# ORD_FV1.net
KiCad netlist of a schematic drawn in Altium Designer
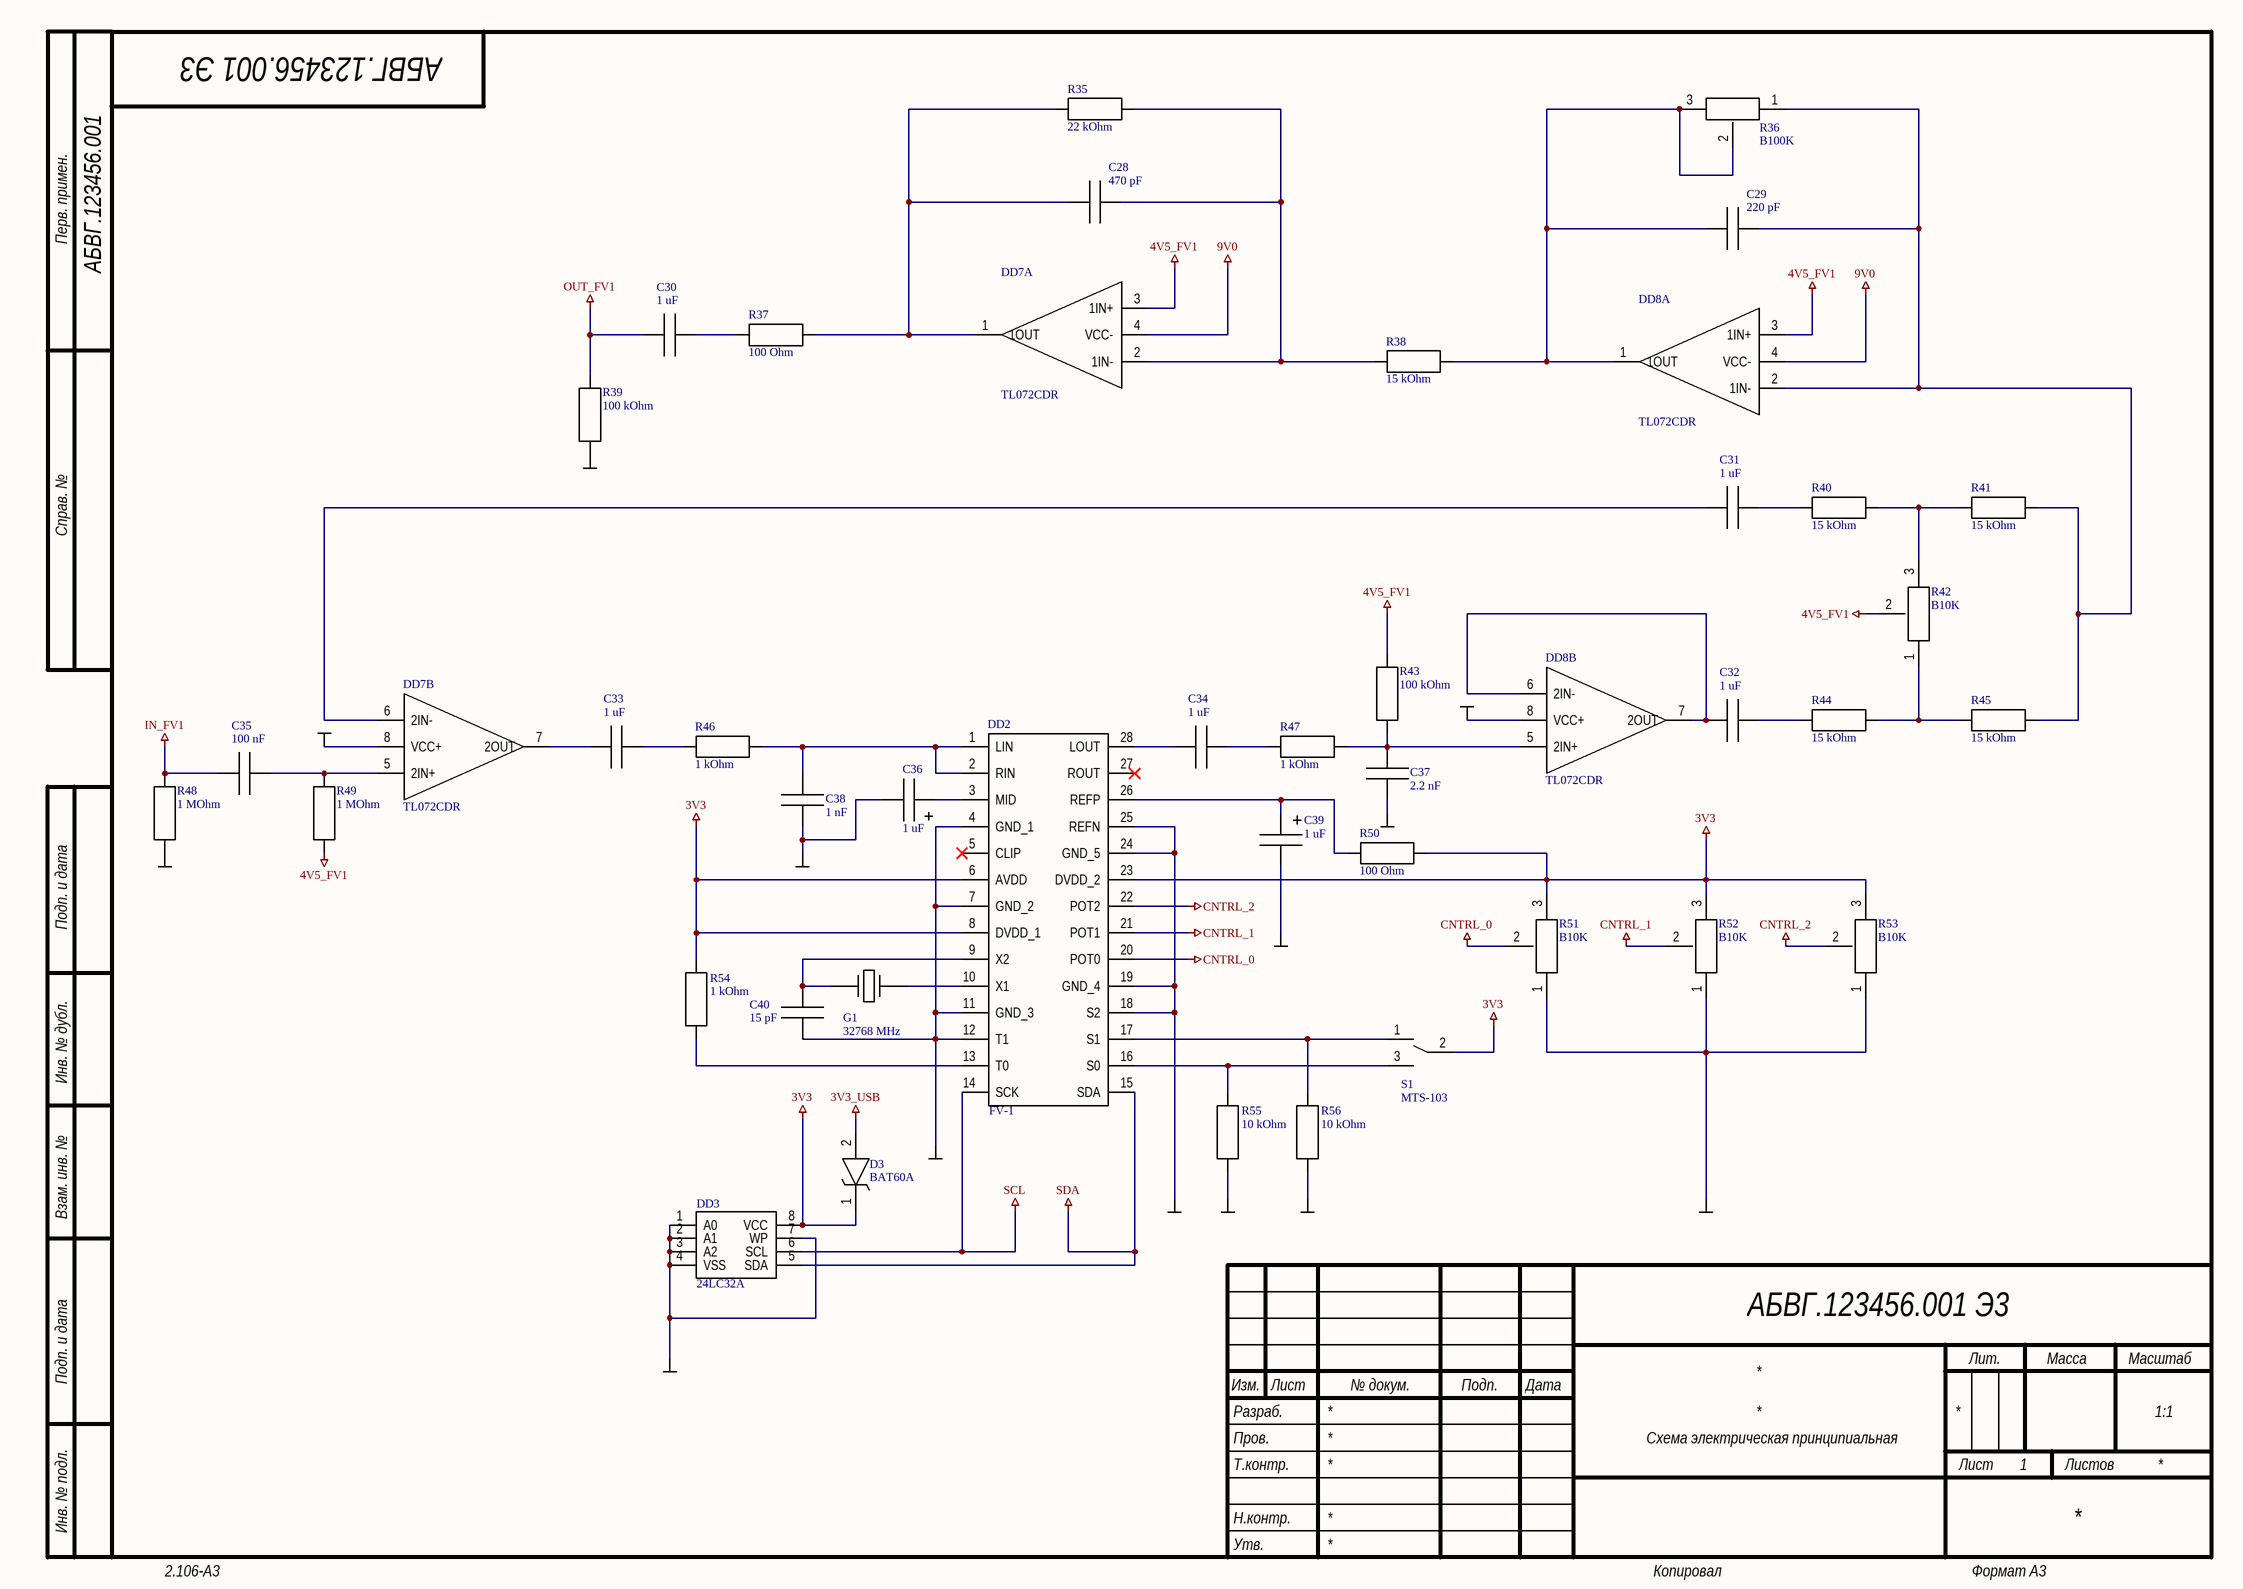
[diagram p0: ORD_FV1.SchDoc]

(export (version "E")
  (design (tool "Eeschema 10.0.6"))
  (components
    (comp (ref "C28")
      (value "470 pF")
      (footprint "C0805[2012]")
      (libsource (lib "Gost_passive_lib") (part "Capacitor"))
    )
    (comp (ref "C29")
      (value "220 pF")
      (footprint "C0805[2012]")
      (libsource (lib "Gost_passive_lib") (part "Capacitor"))
    )
    (comp (ref "C30")
      (value "1 uF")
      (footprint "C0805[2012]")
      (libsource (lib "Gost_passive_lib") (part "Capacitor"))
    )
    (comp (ref "C31")
      (value "1 uF")
      (footprint "C0805[2012]")
      (libsource (lib "Gost_passive_lib") (part "Capacitor"))
    )
    (comp (ref "C32")
      (value "1 uF")
      (footprint "C0805[2012]")
      (libsource (lib "Gost_passive_lib") (part "Capacitor"))
    )
    (comp (ref "C33")
      (value "1 uF")
      (footprint "C0805[2012]")
      (libsource (lib "Gost_passive_lib") (part "Capacitor"))
    )
    (comp (ref "C34")
      (value "1 uF")
      (footprint "C0805[2012]")
      (libsource (lib "Gost_passive_lib") (part "Capacitor"))
    )
    (comp (ref "C35")
      (value "100 nF")
      (footprint "C0805[2012]")
      (libsource (lib "Gost_passive_lib") (part "Capacitor"))
    )
    (comp (ref "C36")
      (value "1 uF")
      (footprint "C3216_CASE-A")
      (libsource (lib "Gost_passive_lib") (part "Capacitor_Pol"))
    )
    (comp (ref "C37")
      (value "2.2 nF")
      (footprint "C0805[2012]")
      (libsource (lib "Gost_passive_lib") (part "Capacitor"))
    )
    (comp (ref "C38")
      (value "1 nF")
      (footprint "C0805[2012]")
      (libsource (lib "Gost_passive_lib") (part "Capacitor"))
    )
    (comp (ref "C39")
      (value "1 uF")
      (footprint "C3216_CASE-A")
      (libsource (lib "Gost_passive_lib") (part "Capacitor_Pol"))
    )
    (comp (ref "C40")
      (value "15 pF")
      (footprint "C0805[2012]")
      (libsource (lib "Gost_passive_lib") (part "Capacitor"))
    )
    (comp (ref "D3")
      (value "BAT60A")
      (footprint "SOD323")
      (description "Diode Schottky 10V 3A Automotive 2-Pin SOD-323 T/R")
      (libsource (lib "Gost_passive_lib") (part "BAT60A"))
    )
    (comp (ref "DD2")
      (value "FV-1")
      (footprint "SOIC28")
      (description "FV-1 Reverb IC, Integrated Stereo ADC & DAC, Integrated Circuit, SOIC-28 300 MIL")
      (fields (field (name "MANUFACTURER_PART_NUMBER") "FV-1 Reverb IC"))
      (libsource (lib "Gost_active_libs") (part "FV-1"))
    )
    (comp (ref "DD3")
      (value "24LC32A")
      (footprint "DIP8_WITH_SOCKET")
      (description "32K I2C Serial EEPROM with Quarter-Array Write-Protect")
      (fields
        (field (name "MANUFACTURER_PART_NUMBER") "24LC32AF-I/P")
        (field (name "MOUSER PART NUMBER") "579-24LC32AF-I/P")
      )
      (libsource (lib "Gost_active_libs") (part "24LC32A"))
    )
    (comp (ref "DD7")
      (value "TL072CDR")
      (footprint "SO8")
      (description "TL072CDR, Dual Operational Amplifier 4 MHz -18 to 18V, 8-Pin SO")
      (fields
        (field (name "MANUFACTURER_PART_NUMBER") "LM358DT")
        (field (name "MOUSER PART NUMBER") "511-LM358DT")
      )
      (libsource (lib "Gost_active_libs") (part "TL072CDR"))
    )
    (comp (ref "DD8")
      (value "TL072CDR")
      (footprint "SO8")
      (description "TL072CDR, Dual Operational Amplifier 4 MHz -18 to 18V, 8-Pin SO")
      (fields
        (field (name "MANUFACTURER_PART_NUMBER") "LM358DT")
        (field (name "MOUSER PART NUMBER") "511-LM358DT")
      )
      (libsource (lib "Gost_active_libs") (part "TL072CDR"))
    )
    (comp (ref "G1")
      (value "32768 MHz")
      (footprint "HC-49")
      (libsource (lib "Gost_passive_lib") (part "Crystal_2pin"))
    )
    (comp (ref "R35")
      (value "22 kOhm")
      (footprint "R0805[2012]")
      (libsource (lib "Gost_passive_lib") (part "Resistor"))
    )
    (comp (ref "R36")
      (value "B100K")
      (footprint "16K1")
      (libsource (lib "Gost_passive_lib") (part "16K1-B (Pot)"))
    )
    (comp (ref "R37")
      (value "100 Ohm")
      (footprint "R0805[2012]")
      (libsource (lib "Gost_passive_lib") (part "Resistor"))
    )
    (comp (ref "R38")
      (value "15 kOhm")
      (footprint "R0805[2012]")
      (libsource (lib "Gost_passive_lib") (part "Resistor"))
    )
    (comp (ref "R39")
      (value "100 kOhm")
      (footprint "R0805[2012]")
      (libsource (lib "Gost_passive_lib") (part "Resistor"))
    )
    (comp (ref "R40")
      (value "15 kOhm")
      (footprint "R0805[2012]")
      (libsource (lib "Gost_passive_lib") (part "Resistor"))
    )
    (comp (ref "R41")
      (value "15 kOhm")
      (footprint "R0805[2012]")
      (libsource (lib "Gost_passive_lib") (part "Resistor"))
    )
    (comp (ref "R42")
      (value "B10K")
      (footprint "16K1")
      (libsource (lib "Gost_passive_lib") (part "16K1-B (Pot)"))
    )
    (comp (ref "R43")
      (value "100 kOhm")
      (footprint "R0805[2012]")
      (libsource (lib "Gost_passive_lib") (part "Resistor"))
    )
    (comp (ref "R44")
      (value "15 kOhm")
      (footprint "R0805[2012]")
      (libsource (lib "Gost_passive_lib") (part "Resistor"))
    )
    (comp (ref "R45")
      (value "15 kOhm")
      (footprint "R0805[2012]")
      (libsource (lib "Gost_passive_lib") (part "Resistor"))
    )
    (comp (ref "R46")
      (value "1 kOhm")
      (footprint "R0805[2012]")
      (libsource (lib "Gost_passive_lib") (part "Resistor"))
    )
    (comp (ref "R47")
      (value "1 kOhm")
      (footprint "R0805[2012]")
      (libsource (lib "Gost_passive_lib") (part "Resistor"))
    )
    (comp (ref "R48")
      (value "1 MOhm")
      (footprint "R0805[2012]")
      (libsource (lib "Gost_passive_lib") (part "Resistor"))
    )
    (comp (ref "R49")
      (value "1 MOhm")
      (footprint "R0805[2012]")
      (libsource (lib "Gost_passive_lib") (part "Resistor"))
    )
    (comp (ref "R50")
      (value "100 Ohm")
      (footprint "R0805[2012]")
      (libsource (lib "Gost_passive_lib") (part "Resistor"))
    )
    (comp (ref "R51")
      (value "B10K")
      (footprint "16K1")
      (libsource (lib "Gost_passive_lib") (part "16K1-B (Pot)"))
    )
    (comp (ref "R52")
      (value "B10K")
      (footprint "16K1")
      (libsource (lib "Gost_passive_lib") (part "16K1-B (Pot)"))
    )
    (comp (ref "R53")
      (value "B10K")
      (footprint "16K1")
      (libsource (lib "Gost_passive_lib") (part "16K1-B (Pot)"))
    )
    (comp (ref "R54")
      (value "1 kOhm")
      (footprint "R0805[2012]")
      (libsource (lib "Gost_passive_lib") (part "Resistor"))
    )
    (comp (ref "R55")
      (value "10 kOhm")
      (footprint "R0805[2012]")
      (libsource (lib "Gost_passive_lib") (part "Resistor"))
    )
    (comp (ref "R56")
      (value "10 kOhm")
      (footprint "R0805[2012]")
      (libsource (lib "Gost_passive_lib") (part "Resistor"))
    )
    (comp (ref "S1")
      (value "MTS-103")
      (footprint "MTS-103")
      (description "Switch, ON-OFF-ON")
      (libsource (lib "Gost_connectors_lib") (part "MTS-103"))
    )
  )
  (nets
    (net (code "1") (name "3V3") (class "Default")
      (node (ref "D3") (pin "1") (pinfunction "K_1") (pintype "passive"))
      (node (ref "DD2") (pin "23") (pinfunction "DVDD_2_23") (pintype "passive"))
      (node (ref "DD2") (pin "6") (pinfunction "AVDD_6") (pintype "passive"))
      (node (ref "DD2") (pin "8") (pinfunction "DVDD_1_8") (pintype "passive"))
      (node (ref "DD3") (pin "8") (pinfunction "VCC_8") (pintype "passive"))
      (node (ref "R50") (pin "1") (pinfunction "1_1") (pintype "passive"))
      (node (ref "R51") (pin "3") (pinfunction "3_3") (pintype "passive"))
      (node (ref "R52") (pin "3") (pinfunction "3_3") (pintype "passive"))
      (node (ref "R53") (pin "3") (pinfunction "3_3") (pintype "passive"))
      (node (ref "R54") (pin "2") (pinfunction "2_2") (pintype "passive"))
      (node (ref "S1") (pin "2") (pinfunction "2_2") (pintype "passive"))
    )
    (net (code "2") (name "3V3_USB") (class "Default")
      (node (ref "D3") (pin "2") (pinfunction "A_2") (pintype "passive"))
    )
    (net (code "3") (name "4V5_FV1") (class "Default")
      (node (ref "DD7") (pin "3") (pinfunction "1IN+_3") (pintype "passive"))
      (node (ref "DD8") (pin "3") (pinfunction "1IN+_3") (pintype "passive"))
      (node (ref "R42") (pin "2") (pinfunction "2_2") (pintype "passive"))
      (node (ref "R43") (pin "1") (pinfunction "1_1") (pintype "passive"))
      (node (ref "R49") (pin "1") (pinfunction "1_1") (pintype "passive"))
    )
    (net (code "4") (name "9V0") (class "Default")
      (node (ref "DD7") (pin "4") (pinfunction "VCC-_4") (pintype "power_in"))
      (node (ref "DD8") (pin "4") (pinfunction "VCC-_4") (pintype "power_in"))
    )
    (net (code "5") (name "CNTRL_0") (class "Default")
      (node (ref "DD2") (pin "20") (pinfunction "POT0_20") (pintype "passive"))
      (node (ref "R51") (pin "2") (pinfunction "2_2") (pintype "passive"))
    )
    (net (code "6") (name "CNTRL_1") (class "Default")
      (node (ref "DD2") (pin "21") (pinfunction "POT1_21") (pintype "passive"))
      (node (ref "R52") (pin "2") (pinfunction "2_2") (pintype "passive"))
    )
    (net (code "7") (name "CNTRL_2") (class "Default")
      (node (ref "DD2") (pin "22") (pinfunction "POT2_22") (pintype "passive"))
      (node (ref "R53") (pin "2") (pinfunction "2_2") (pintype "passive"))
    )
    (net (code "8") (name "GND") (class "Default")
      (node (ref "C36") (pin "2") (pinfunction "2_2") (pintype "passive"))
      (node (ref "C37") (pin "1") (pinfunction "1_1") (pintype "passive"))
      (node (ref "C38") (pin "1") (pinfunction "1_1") (pintype "passive"))
      (node (ref "C39") (pin "2") (pinfunction "2_2") (pintype "passive"))
      (node (ref "C40") (pin "2") (pinfunction "2_2") (pintype "passive"))
      (node (ref "DD2") (pin "11") (pinfunction "GND_3_11") (pintype "passive"))
      (node (ref "DD2") (pin "12") (pinfunction "T1_12") (pintype "passive"))
      (node (ref "DD2") (pin "18") (pinfunction "S2_18") (pintype "passive"))
      (node (ref "DD2") (pin "19") (pinfunction "GND_4_19") (pintype "passive"))
      (node (ref "DD2") (pin "24") (pinfunction "GND_5_24") (pintype "passive"))
      (node (ref "DD2") (pin "25") (pinfunction "REFN_25") (pintype "passive"))
      (node (ref "DD2") (pin "4") (pinfunction "GND_1_4") (pintype "passive"))
      (node (ref "DD2") (pin "7") (pinfunction "GND_2_7") (pintype "passive"))
      (node (ref "DD3") (pin "1") (pinfunction "A0_1") (pintype "passive"))
      (node (ref "DD3") (pin "2") (pinfunction "A1_2") (pintype "passive"))
      (node (ref "DD3") (pin "3") (pinfunction "A2_3") (pintype "passive"))
      (node (ref "DD3") (pin "4") (pinfunction "VSS_4") (pintype "passive"))
      (node (ref "DD3") (pin "7") (pinfunction "WP_7") (pintype "passive"))
      (node (ref "DD7") (pin "8") (pinfunction "VCC+_8") (pintype "power_in"))
      (node (ref "DD8") (pin "8") (pinfunction "VCC+_8") (pintype "power_in"))
      (node (ref "R39") (pin "1") (pinfunction "1_1") (pintype "passive"))
      (node (ref "R48") (pin "1") (pinfunction "1_1") (pintype "passive"))
      (node (ref "R51") (pin "1") (pinfunction "1_1") (pintype "passive"))
      (node (ref "R52") (pin "1") (pinfunction "1_1") (pintype "passive"))
      (node (ref "R53") (pin "1") (pinfunction "1_1") (pintype "passive"))
      (node (ref "R55") (pin "1") (pinfunction "1_1") (pintype "passive"))
      (node (ref "R56") (pin "1") (pinfunction "1_1") (pintype "passive"))
    )
    (net (code "9") (name "IN_FV1") (class "Default")
      (node (ref "C35") (pin "1") (pinfunction "1_1") (pintype "passive"))
      (node (ref "R48") (pin "2") (pinfunction "2_2") (pintype "passive"))
    )
    (net (code "10") (name "Net-(C30-Pad2)") (class "Default")
      (node (ref "C30") (pin "2") (pinfunction "2_2") (pintype "passive"))
      (node (ref "R37") (pin "2") (pinfunction "2_2") (pintype "passive"))
    )
    (net (code "11") (name "Net-(C31-Pad2)") (class "Default")
      (node (ref "C31") (pin "2") (pinfunction "2_2") (pintype "passive"))
      (node (ref "R40") (pin "2") (pinfunction "2_2") (pintype "passive"))
    )
    (net (code "12") (name "Net-(C32-Pad2)") (class "Default")
      (node (ref "C32") (pin "2") (pinfunction "2_2") (pintype "passive"))
      (node (ref "R44") (pin "2") (pinfunction "2_2") (pintype "passive"))
    )
    (net (code "13") (name "Net-(C33-Pad2)") (class "Default")
      (node (ref "C33") (pin "2") (pinfunction "2_2") (pintype "passive"))
      (node (ref "R46") (pin "2") (pinfunction "2_2") (pintype "passive"))
    )
    (net (code "14") (name "Net-(C34-Pad2)") (class "Default")
      (node (ref "C34") (pin "2") (pinfunction "2_2") (pintype "passive"))
      (node (ref "R47") (pin "2") (pinfunction "2_2") (pintype "passive"))
    )
    (net (code "15") (name "Net-(DD2-LIN)") (class "Default")
      (node (ref "C38") (pin "2") (pinfunction "2_2") (pintype "passive"))
      (node (ref "DD2") (pin "1") (pinfunction "LIN_1") (pintype "passive"))
      (node (ref "DD2") (pin "2") (pinfunction "RIN_2") (pintype "passive"))
      (node (ref "R46") (pin "1") (pinfunction "1_1") (pintype "passive"))
    )
    (net (code "16") (name "Net-(DD2-LOUT)") (class "Default")
      (node (ref "C34") (pin "1") (pinfunction "1_1") (pintype "passive"))
      (node (ref "DD2") (pin "28") (pinfunction "LOUT_28") (pintype "passive"))
    )
    (net (code "17") (name "Net-(DD2-MID)") (class "Default")
      (node (ref "C36") (pin "1") (pinfunction "1_1") (pintype "passive"))
      (node (ref "DD2") (pin "3") (pinfunction "MID_3") (pintype "passive"))
    )
    (net (code "18") (name "Net-(DD2-REFP)") (class "Default")
      (node (ref "C39") (pin "1") (pinfunction "1_1") (pintype "passive"))
      (node (ref "DD2") (pin "26") (pinfunction "REFP_26") (pintype "passive"))
      (node (ref "R50") (pin "2") (pinfunction "2_2") (pintype "passive"))
    )
    (net (code "19") (name "Net-(DD2-S0)") (class "Default")
      (node (ref "DD2") (pin "16") (pinfunction "S0_16") (pintype "passive"))
      (node (ref "R55") (pin "2") (pinfunction "2_2") (pintype "passive"))
      (node (ref "S1") (pin "3") (pinfunction "3_3") (pintype "passive"))
    )
    (net (code "20") (name "Net-(DD2-S1)") (class "Default")
      (node (ref "DD2") (pin "17") (pinfunction "S1_17") (pintype "passive"))
      (node (ref "R56") (pin "2") (pinfunction "2_2") (pintype "passive"))
      (node (ref "S1") (pin "1") (pinfunction "1_1") (pintype "passive"))
    )
    (net (code "21") (name "Net-(DD2-T0)") (class "Default")
      (node (ref "DD2") (pin "13") (pinfunction "T0_13") (pintype "passive"))
      (node (ref "R54") (pin "1") (pinfunction "1_1") (pintype "passive"))
    )
    (net (code "22") (name "Net-(DD2-X1)") (class "Default")
      (node (ref "DD2") (pin "10") (pinfunction "X1_10") (pintype "passive"))
      (node (ref "G1") (pin "2") (pinfunction "2_2") (pintype "passive"))
    )
    (net (code "23") (name "Net-(DD2-X2)") (class "Default")
      (node (ref "C40") (pin "1") (pinfunction "1_1") (pintype "passive"))
      (node (ref "DD2") (pin "9") (pinfunction "X2_9") (pintype "passive"))
      (node (ref "G1") (pin "1") (pinfunction "1_1") (pintype "passive"))
    )
    (net (code "24") (name "Net-(DD7A-1IN-)") (class "Default")
      (node (ref "C28") (pin "2") (pinfunction "2_2") (pintype "passive"))
      (node (ref "DD7") (pin "2") (pinfunction "1IN-_2") (pintype "passive"))
      (node (ref "R35") (pin "1") (pinfunction "1_1") (pintype "passive"))
      (node (ref "R38") (pin "2") (pinfunction "2_2") (pintype "passive"))
    )
    (net (code "25") (name "Net-(DD7A-1OUT)") (class "Default")
      (node (ref "C28") (pin "1") (pinfunction "1_1") (pintype "passive"))
      (node (ref "DD7") (pin "1") (pinfunction "1OUT_1") (pintype "passive"))
      (node (ref "R35") (pin "2") (pinfunction "2_2") (pintype "passive"))
      (node (ref "R37") (pin "1") (pinfunction "1_1") (pintype "passive"))
    )
    (net (code "26") (name "Net-(DD7B-2IN+)") (class "Default")
      (node (ref "C35") (pin "2") (pinfunction "2_2") (pintype "passive"))
      (node (ref "DD7") (pin "5") (pinfunction "2IN+_5") (pintype "passive"))
      (node (ref "R49") (pin "2") (pinfunction "2_2") (pintype "passive"))
    )
    (net (code "27") (name "Net-(DD7B-2IN-)") (class "Default")
      (node (ref "C31") (pin "1") (pinfunction "1_1") (pintype "passive"))
      (node (ref "DD7") (pin "6") (pinfunction "2IN-_6") (pintype "passive"))
    )
    (net (code "28") (name "Net-(DD7B-2OUT)") (class "Default")
      (node (ref "C33") (pin "1") (pinfunction "1_1") (pintype "passive"))
      (node (ref "DD7") (pin "7") (pinfunction "2OUT_7") (pintype "passive"))
    )
    (net (code "29") (name "Net-(DD8A-1IN-)") (class "Default")
      (node (ref "C29") (pin "2") (pinfunction "2_2") (pintype "passive"))
      (node (ref "DD8") (pin "2") (pinfunction "1IN-_2") (pintype "passive"))
      (node (ref "R36") (pin "1") (pinfunction "1_1") (pintype "passive"))
      (node (ref "R41") (pin "1") (pinfunction "1_1") (pintype "passive"))
      (node (ref "R45") (pin "1") (pinfunction "1_1") (pintype "passive"))
    )
    (net (code "30") (name "Net-(DD8A-1OUT)") (class "Default")
      (node (ref "C29") (pin "1") (pinfunction "1_1") (pintype "passive"))
      (node (ref "DD8") (pin "1") (pinfunction "1OUT_1") (pintype "passive"))
      (node (ref "R36") (pin "2") (pinfunction "2_2") (pintype "passive"))
      (node (ref "R36") (pin "3") (pinfunction "3_3") (pintype "passive"))
      (node (ref "R38") (pin "1") (pinfunction "1_1") (pintype "passive"))
    )
    (net (code "31") (name "Net-(DD8B-2IN+)") (class "Default")
      (node (ref "C37") (pin "2") (pinfunction "2_2") (pintype "passive"))
      (node (ref "DD8") (pin "5") (pinfunction "2IN+_5") (pintype "passive"))
      (node (ref "R43") (pin "2") (pinfunction "2_2") (pintype "passive"))
      (node (ref "R47") (pin "1") (pinfunction "1_1") (pintype "passive"))
    )
    (net (code "32") (name "Net-(DD8B-2IN-)") (class "Default")
      (node (ref "C32") (pin "1") (pinfunction "1_1") (pintype "passive"))
      (node (ref "DD8") (pin "6") (pinfunction "2IN-_6") (pintype "passive"))
      (node (ref "DD8") (pin "7") (pinfunction "2OUT_7") (pintype "passive"))
    )
    (net (code "33") (name "Net-(R40-Pad1)") (class "Default")
      (node (ref "R40") (pin "1") (pinfunction "1_1") (pintype "passive"))
      (node (ref "R41") (pin "2") (pinfunction "2_2") (pintype "passive"))
      (node (ref "R42") (pin "3") (pinfunction "3_3") (pintype "passive"))
    )
    (net (code "34") (name "Net-(R42-Pad1)") (class "Default")
      (node (ref "R42") (pin "1") (pinfunction "1_1") (pintype "passive"))
      (node (ref "R44") (pin "1") (pinfunction "1_1") (pintype "passive"))
      (node (ref "R45") (pin "2") (pinfunction "2_2") (pintype "passive"))
    )
    (net (code "35") (name "OUT_FV1") (class "Default")
      (node (ref "C30") (pin "1") (pinfunction "1_1") (pintype "passive"))
      (node (ref "R39") (pin "2") (pinfunction "2_2") (pintype "passive"))
    )
    (net (code "36") (name "SCL") (class "Default")
      (node (ref "DD2") (pin "14") (pinfunction "SCK_14") (pintype "passive"))
      (node (ref "DD3") (pin "6") (pinfunction "SCL_6") (pintype "passive"))
    )
    (net (code "37") (name "SDA") (class "Default")
      (node (ref "DD2") (pin "15") (pinfunction "SDA_15") (pintype "passive"))
      (node (ref "DD3") (pin "5") (pinfunction "SDA_5") (pintype "passive"))
    )
    (net (code "38") (name "unconnected-(DD2-CLIP-Pad5)") (class "Default")
      (node (ref "DD2") (pin "5") (pinfunction "CLIP_5") (pintype "passive+no_connect"))
    )
    (net (code "39") (name "unconnected-(DD2-ROUT-Pad27)") (class "Default")
      (node (ref "DD2") (pin "27") (pinfunction "ROUT_27") (pintype "passive+no_connect"))
    )
  )
)
